# ProProject_ADS1292R-TestBoard.net
KiCad netlist of a schematic drawn in EasyEDA Pro
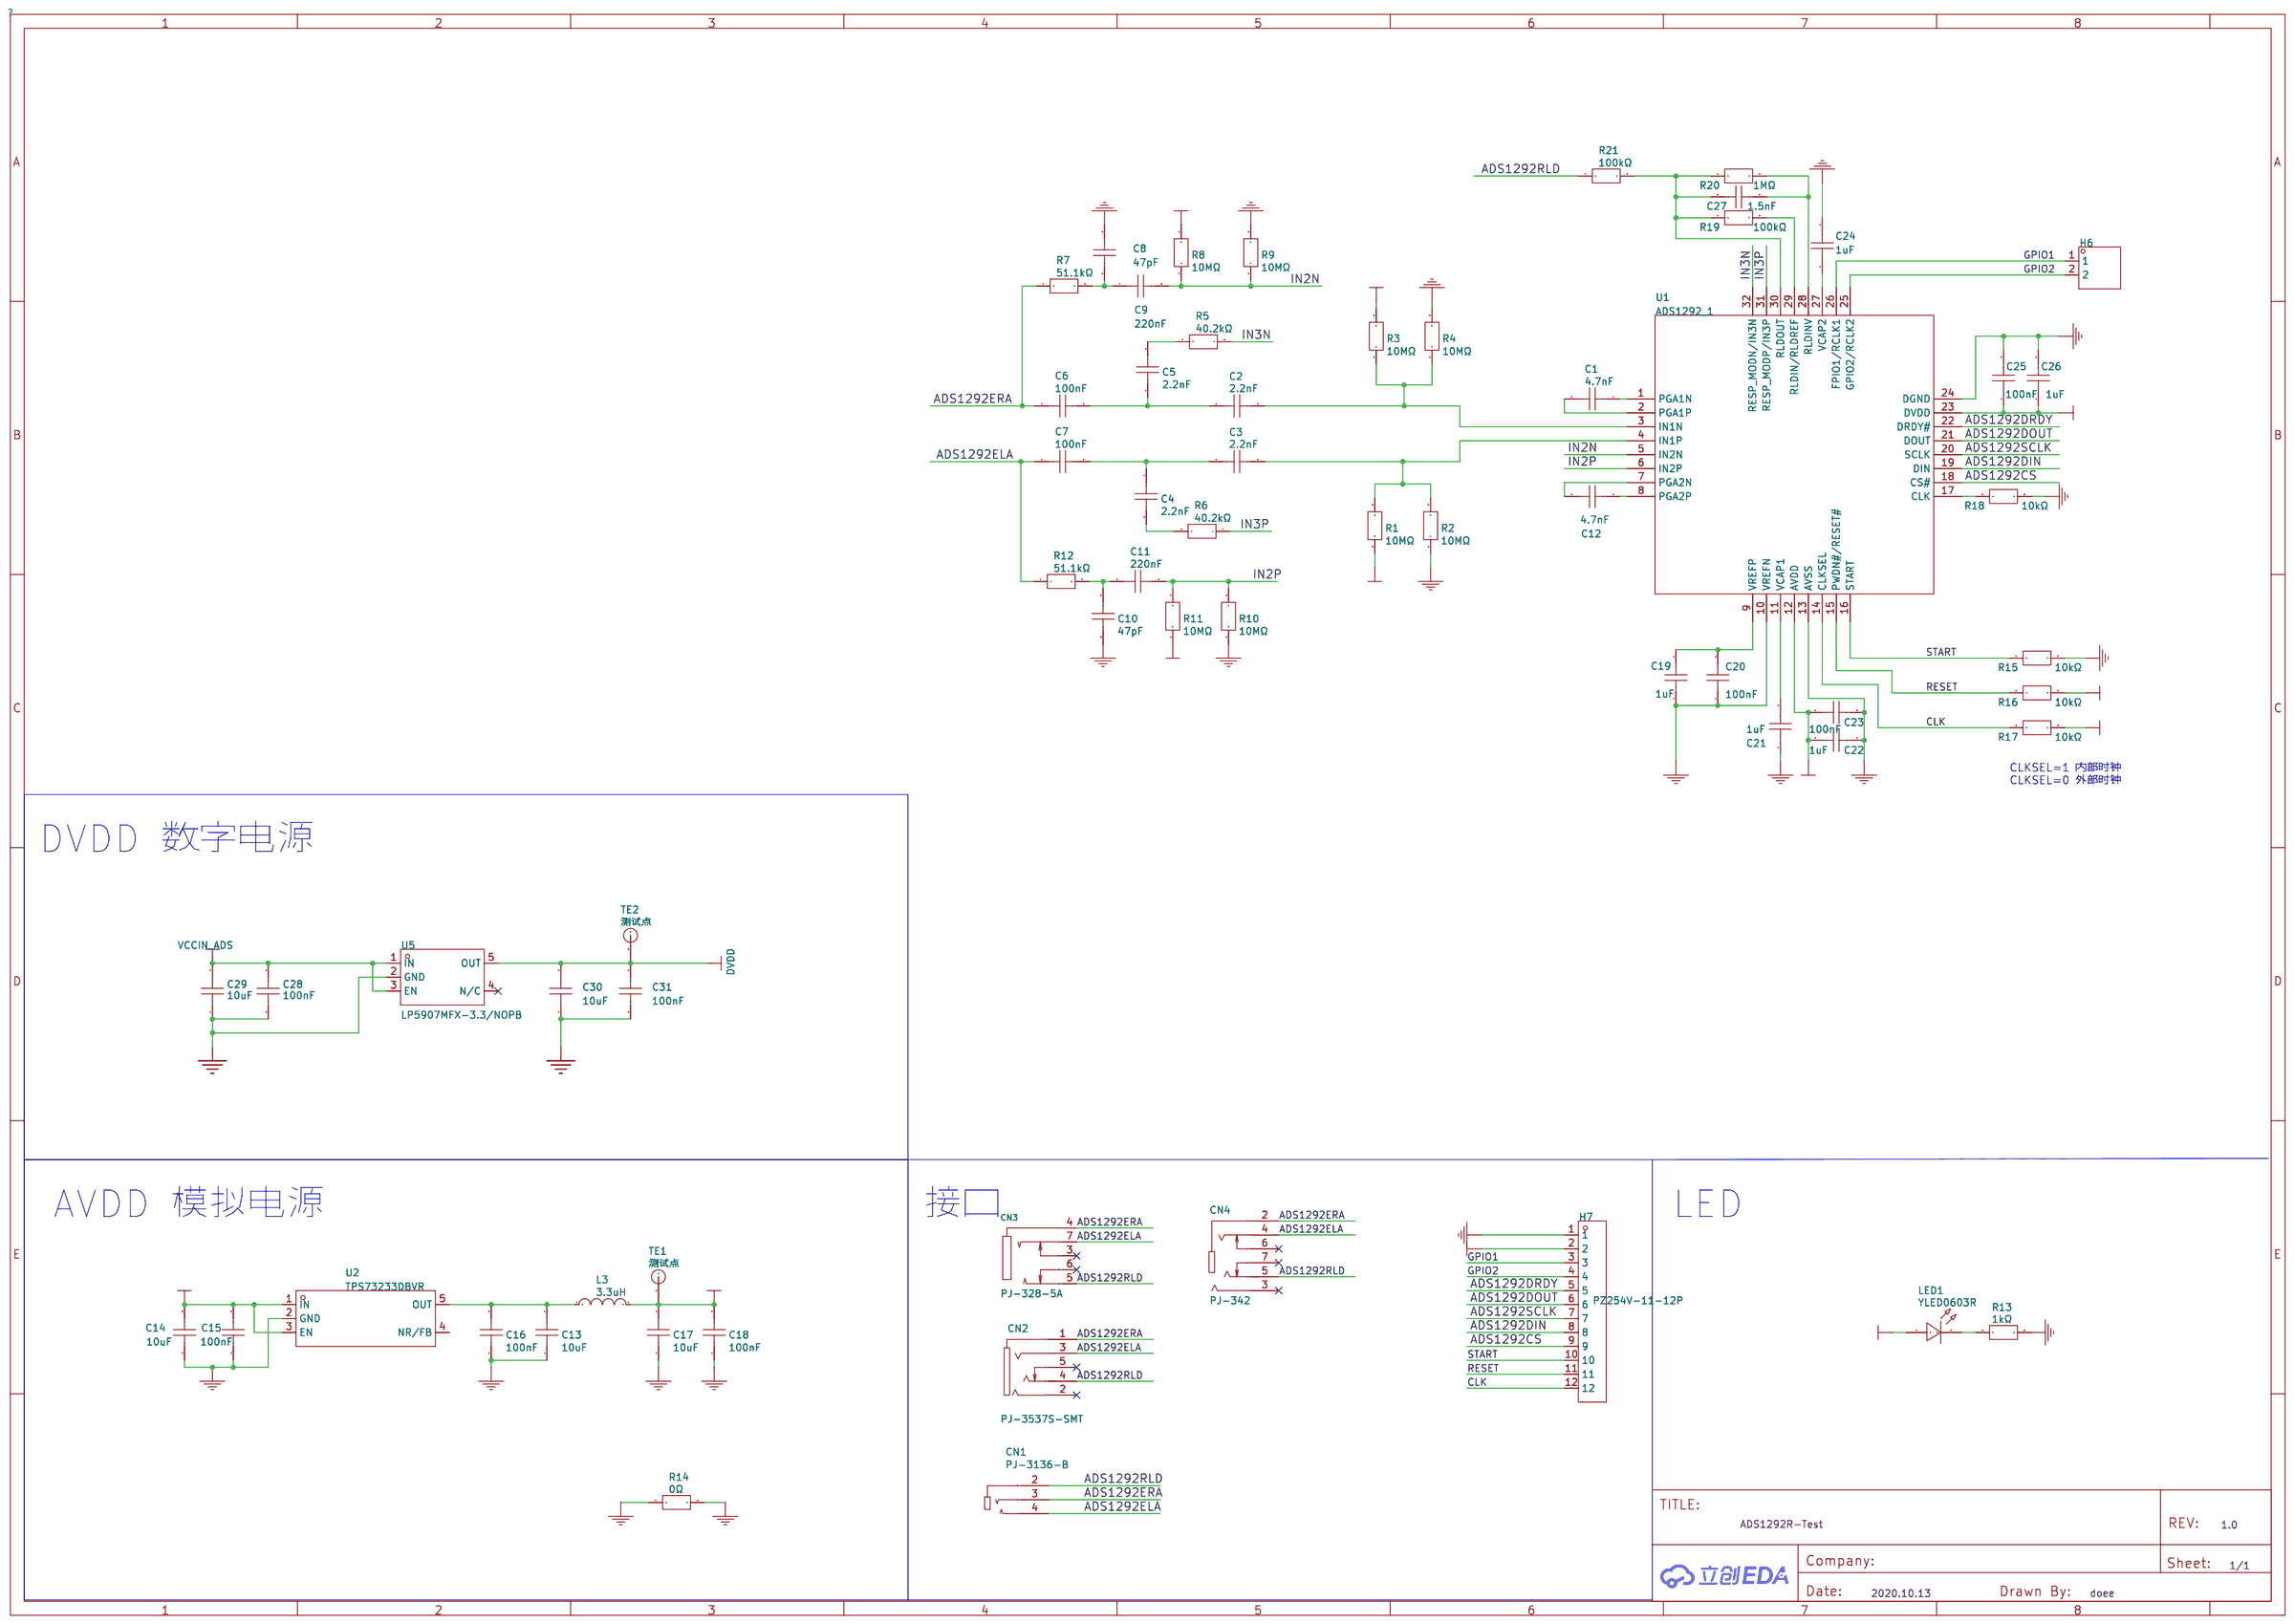
[diagram p0: schematic sheet]

(export (version "E")
  (design (tool "Eeschema 10.0.6"))
  (components
    (comp (ref "C1")
      (value "4.7nF")
      (footprint "easyedapro:C0603")
      (description "容值:4.7nF;精度:±5%;额定电压:50V;材质(温度系数):X7R;")
      (fields
        (field (name "Manufacturer Part") "CC0603JRX7R9BB472")
        (field (name "Manufacturer") "YAGEO(国巨)")
      )
      (libsource (lib "easyedapro") (part "4.7n"))
    )
    (comp (ref "C2")
      (value "2.2nF")
      (footprint "easyedapro:C0603")
      (description "容值:2.2nF;精度:±5%;额定电压:50V;材质(温度系数):NP0;")
      (fields
        (field (name "Manufacturer Part") "CC0603JRNPO9BN222")
        (field (name "Manufacturer") "YAGEO(国巨)")
      )
      (libsource (lib "easyedapro") (part "2.2n"))
    )
    (comp (ref "C3")
      (value "2.2nF")
      (footprint "easyedapro:C0603")
      (description "容值:2.2nF;精度:±5%;额定电压:50V;材质(温度系数):NP0;")
      (fields
        (field (name "Manufacturer Part") "CC0603JRNPO9BN222")
        (field (name "Manufacturer") "YAGEO(国巨)")
      )
      (libsource (lib "easyedapro") (part "2.2n"))
    )
    (comp (ref "C4")
      (value "2.2nF")
      (footprint "easyedapro:C0603")
      (description "容值:2.2nF;精度:±5%;额定电压:50V;材质(温度系数):NP0;")
      (fields
        (field (name "Manufacturer Part") "CC0603JRNPO9BN222")
        (field (name "Manufacturer") "YAGEO(国巨)")
      )
      (libsource (lib "easyedapro") (part "2.2n"))
    )
    (comp (ref "C5")
      (value "2.2nF")
      (footprint "easyedapro:C0603")
      (description "容值:2.2nF;精度:±5%;额定电压:50V;材质(温度系数):NP0;")
      (fields
        (field (name "Manufacturer Part") "CC0603JRNPO9BN222")
        (field (name "Manufacturer") "YAGEO(国巨)")
      )
      (libsource (lib "easyedapro") (part "2.2n"))
    )
    (comp (ref "C6")
      (value "100nF")
      (footprint "easyedapro:C0603")
      (description "容值:100nF;精度:±10%;额定电压:50V;材质(温度系数):X7R;")
      (fields
        (field (name "Manufacturer Part") "CC0603KRX7R9BB104")
        (field (name "Manufacturer") "YAGEO(国巨)")
      )
      (libsource (lib "easyedapro") (part "0.1u"))
    )
    (comp (ref "C7")
      (value "100nF")
      (footprint "easyedapro:C0603")
      (description "容值:100nF;精度:±10%;额定电压:50V;材质(温度系数):X7R;")
      (fields
        (field (name "Manufacturer Part") "CC0603KRX7R9BB104")
        (field (name "Manufacturer") "YAGEO(国巨)")
      )
      (libsource (lib "easyedapro") (part "0.1u"))
    )
    (comp (ref "C8")
      (value "47pF")
      (footprint "easyedapro:C0603")
      (description "容值:47pF;精度:±5%;额定电压:50V;材质(温度系数):C0G;")
      (fields
        (field (name "Manufacturer Part") "CL10C470JB8NNNC")
        (field (name "Manufacturer") "SAMSUNG(三星)")
      )
      (libsource (lib "easyedapro") (part "47p"))
    )
    (comp (ref "C9")
      (value "220nF")
      (footprint "easyedapro:C0603")
      (description "容值:220nF;精度:±10%;额定电压:25V;材质(温度系数):X7R;")
      (fields
        (field (name "Manufacturer Part") "CL10B224KA8NNNC")
        (field (name "Manufacturer") "SAMSUNG(三星)")
      )
      (libsource (lib "easyedapro") (part "220n"))
    )
    (comp (ref "C10")
      (value "47pF")
      (footprint "easyedapro:C0603")
      (description "容值:47pF;精度:±5%;额定电压:50V;材质(温度系数):C0G;")
      (fields
        (field (name "Manufacturer Part") "CL10C470JB8NNNC")
        (field (name "Manufacturer") "SAMSUNG(三星)")
      )
      (libsource (lib "easyedapro") (part "47p"))
    )
    (comp (ref "C11")
      (value "220nF")
      (footprint "easyedapro:C0603")
      (description "容值:220nF;精度:±10%;额定电压:25V;材质(温度系数):X7R;")
      (fields
        (field (name "Manufacturer Part") "CL10B224KA8NNNC")
        (field (name "Manufacturer") "SAMSUNG(三星)")
      )
      (libsource (lib "easyedapro") (part "220n"))
    )
    (comp (ref "C12")
      (value "4.7nF")
      (footprint "easyedapro:C0603")
      (description "容值:4.7nF;精度:±5%;额定电压:50V;材质(温度系数):X7R;")
      (fields
        (field (name "Manufacturer Part") "CC0603JRX7R9BB472")
        (field (name "Manufacturer") "YAGEO(国巨)")
      )
      (libsource (lib "easyedapro") (part "4.7n"))
    )
    (comp (ref "C13")
      (value "10uF")
      (footprint "easyedapro:C0603")
      (description "容值:10uF;精度:±10%;额定电压:10V;材质(温度系数):X5R;")
      (fields
        (field (name "Manufacturer Part") "CL10A106KP8NNNC")
        (field (name "Manufacturer") "SAMSUNG(三星)")
      )
      (libsource (lib "easyedapro") (part "10u"))
    )
    (comp (ref "C14")
      (value "10uF")
      (footprint "easyedapro:C0603")
      (description "容值:10uF;精度:±10%;额定电压:10V;材质(温度系数):X5R;")
      (fields
        (field (name "Manufacturer Part") "CL10A106KP8NNNC")
        (field (name "Manufacturer") "SAMSUNG(三星)")
      )
      (libsource (lib "easyedapro") (part "10u"))
    )
    (comp (ref "C15")
      (value "100nF")
      (footprint "easyedapro:C0603")
      (description "容值:100nF;精度:±10%;额定电压:50V;材质(温度系数):X7R;")
      (fields
        (field (name "Manufacturer Part") "CC0603KRX7R9BB104")
        (field (name "Manufacturer") "YAGEO(国巨)")
      )
      (libsource (lib "easyedapro") (part "0.1u"))
    )
    (comp (ref "C16")
      (value "100nF")
      (footprint "easyedapro:C0603")
      (description "容值:100nF;精度:±10%;额定电压:50V;材质(温度系数):X7R;")
      (fields
        (field (name "Manufacturer Part") "CC0603KRX7R9BB104")
        (field (name "Manufacturer") "YAGEO(国巨)")
      )
      (libsource (lib "easyedapro") (part "0.1u"))
    )
    (comp (ref "C17")
      (value "10uF")
      (footprint "easyedapro:C0603")
      (description "容值:10uF;精度:±10%;额定电压:10V;材质(温度系数):X5R;")
      (fields
        (field (name "Manufacturer Part") "CL10A106KP8NNNC")
        (field (name "Manufacturer") "SAMSUNG(三星)")
      )
      (libsource (lib "easyedapro") (part "10u"))
    )
    (comp (ref "C18")
      (value "100nF")
      (footprint "easyedapro:C0603")
      (description "容值:100nF;精度:±10%;额定电压:50V;材质(温度系数):X7R;")
      (fields
        (field (name "Manufacturer Part") "CC0603KRX7R9BB104")
        (field (name "Manufacturer") "YAGEO(国巨)")
      )
      (libsource (lib "easyedapro") (part "0.1u"))
    )
    (comp (ref "C19")
      (value "1uF")
      (footprint "easyedapro:C0603")
      (description "容值:1uF;精度:±10%;额定电压:50V;材质(温度系数):X5R;")
      (fields
        (field (name "Manufacturer Part") "CL10A105KB8NNNC")
        (field (name "Manufacturer") "SAMSUNG(三星)")
      )
      (libsource (lib "easyedapro") (part "1u"))
    )
    (comp (ref "C20")
      (value "100nF")
      (footprint "easyedapro:C0603")
      (description "容值:100nF;精度:±10%;额定电压:50V;材质(温度系数):X7R;")
      (fields
        (field (name "Manufacturer Part") "CC0603KRX7R9BB104")
        (field (name "Manufacturer") "YAGEO(国巨)")
      )
      (libsource (lib "easyedapro") (part "0.1u"))
    )
    (comp (ref "C21")
      (value "1uF")
      (footprint "easyedapro:C0603")
      (description "容值:1uF;精度:±10%;额定电压:50V;材质(温度系数):X5R;")
      (fields
        (field (name "Manufacturer Part") "CL10A105KB8NNNC")
        (field (name "Manufacturer") "SAMSUNG(三星)")
      )
      (libsource (lib "easyedapro") (part "1u"))
    )
    (comp (ref "C22")
      (value "1uF")
      (footprint "easyedapro:C0603")
      (description "容值:1uF;精度:±10%;额定电压:50V;材质(温度系数):X5R;")
      (fields
        (field (name "Manufacturer Part") "CL10A105KB8NNNC")
        (field (name "Manufacturer") "SAMSUNG(三星)")
      )
      (libsource (lib "easyedapro") (part "1u"))
    )
    (comp (ref "C23")
      (value "100nF")
      (footprint "easyedapro:C0603")
      (description "容值:100nF;精度:±10%;额定电压:50V;材质(温度系数):X7R;")
      (fields
        (field (name "Manufacturer Part") "CC0603KRX7R9BB104")
        (field (name "Manufacturer") "YAGEO(国巨)")
      )
      (libsource (lib "easyedapro") (part "0.1u"))
    )
    (comp (ref "C24")
      (value "1uF")
      (footprint "easyedapro:C0603")
      (description "容值:1uF;精度:±10%;额定电压:50V;材质(温度系数):X5R;")
      (fields
        (field (name "Manufacturer Part") "CL10A105KB8NNNC")
        (field (name "Manufacturer") "SAMSUNG(三星)")
      )
      (libsource (lib "easyedapro") (part "1u"))
    )
    (comp (ref "C25")
      (value "100nF")
      (footprint "easyedapro:C0603")
      (description "容值:100nF;精度:±10%;额定电压:50V;材质(温度系数):X7R;")
      (fields
        (field (name "Manufacturer Part") "CC0603KRX7R9BB104")
        (field (name "Manufacturer") "YAGEO(国巨)")
      )
      (libsource (lib "easyedapro") (part "0.1u"))
    )
    (comp (ref "C26")
      (value "1uF")
      (footprint "easyedapro:C0603")
      (description "容值:1uF;精度:±10%;额定电压:50V;材质(温度系数):X5R;")
      (fields
        (field (name "Manufacturer Part") "CL10A105KB8NNNC")
        (field (name "Manufacturer") "SAMSUNG(三星)")
      )
      (libsource (lib "easyedapro") (part "1u"))
    )
    (comp (ref "C27")
      (value "1.5nF")
      (footprint "easyedapro:C0603")
      (description "容值:1.5nF;精度:±10%;额定电压:50V;材质(温度系数):-;")
      (fields (field (name "Manufacturer") "SAMSUNG(三星)") (field (name "Tolerance") "±10%"))
      (libsource (lib "easyedapro") (part "1.5n"))
    )
    (comp (ref "C28")
      (value "100nF")
      (footprint "easyedapro:C0603")
      (fields
        (field (name "Manufacturer Part") "CC0603KRX7R9BB104")
        (field (name "Manufacturer") "YAGEO(国巨)")
        (field (name "Tolerance") "±10%")
      )
      (libsource (lib "easyedapro") (part "CapAcitance"))
    )
    (comp (ref "C29")
      (value "10uF")
      (footprint "easyedapro:C0603")
      (fields
        (field (name "Manufacturer Part") "CL10A106KP8NNNC")
        (field (name "Manufacturer") "SAMSUNG(三星)")
        (field (name "Tolerance") "±10%")
      )
      (libsource (lib "easyedapro") (part "CapAcitance"))
    )
    (comp (ref "C30")
      (value "10uF")
      (footprint "easyedapro:C0603")
      (fields
        (field (name "Manufacturer Part") "CL10A106KP8NNNC")
        (field (name "Manufacturer") "SAMSUNG(三星)")
        (field (name "Tolerance") "±10%")
      )
      (libsource (lib "easyedapro") (part "CapAcitance"))
    )
    (comp (ref "C31")
      (value "100nF")
      (footprint "easyedapro:C0603")
      (fields
        (field (name "Manufacturer Part") "CC0603KRX7R9BB104")
        (field (name "Manufacturer") "YAGEO(国巨)")
        (field (name "Tolerance") "±10%")
      )
      (libsource (lib "easyedapro") (part "CapAcitance"))
    )
    (comp (ref "CN1")
      (value "PJ-3136-B")
      (footprint "easyedapro:AUDIO-TH_PJ-3136-B")
      (libsource (lib "easyedapro") (part "PJ-3136-B"))
    )
    (comp (ref "CN2")
      (value "PJ-3537S-SMT")
      (footprint "easyedapro:AUDIO-SMD_PJ-3537S")
      (description "连接器类型:3.5mm耳机座;额定电流:500mA;额定电压:30V;工作温度范围:-30°C~+70°C;焊接温度(最大值):235°C;")
      (fields (field (name "Manufacturer") "XKB Connectivity(中国星坤)"))
      (libsource (lib "easyedapro") (part "PJ-3537S"))
    )
    (comp (ref "CN3")
      (value "PJ-328-5A")
      (footprint "easyedapro:AUDIO-SMD_PJ-328-5A")
      (description "连接器类型:3.5mm耳机座;额定电流:500mA;额定电压:30V;工作温度范围:-20°C~+70°C;")
      (fields (field (name "Manufacturer") "韩国韩荣"))
      (libsource (lib "easyedapro") (part "PJ-328-5A"))
    )
    (comp (ref "CN4")
      (value "PJ-342")
      (footprint "easyedapro:AUDIO-SMD_PJ-342")
      (description "连接器类型:3.5mm耳机座;额定电流:500mA;额定电压:30V;工作温度范围:-30°C~+70°C;")
      (fields (field (name "Manufacturer") "SHOU HAN(首韩)"))
      (libsource (lib "easyedapro") (part "PJ-342"))
    )
    (comp (ref "H6")
      (value "~")
      (footprint "easyedapro:HDR-TH_2P-P2.54-V-M-1")
      (libsource (lib "easyedapro") (part "210S-1*2P L=11.6MMGold-plated black"))
    )
    (comp (ref "H7")
      (value "PZ254V-11-12P")
      (footprint "easyedapro:HDR-TH_12P-P2.54-V-M")
      (fields (field (name "Manufacturer") "XFCN(兴飞)"))
      (libsource (lib "easyedapro") (part "HDR_2.54-1x12P"))
    )
    (comp (ref "L3")
      (value "3.3uH")
      (footprint "easyedapro:L0805")
      (libsource (lib "easyedapro") (part "3.3uH"))
    )
    (comp (ref "LED1")
      (value "YLED0603R")
      (footprint "easyedapro:LED0603_RED")
      (fields (field (name "Manufacturer") "YONGYUTAI(永裕泰)"))
      (libsource (lib "easyedapro") (part "LED-0603_R"))
    )
    (comp (ref "R1")
      (value "10MΩ")
      (footprint "easyedapro:R0603")
      (description "电阻类型:厚膜电阻;阻值:10MΩ;精度:±1%;功率:100mW;最大工作电压:75V;温度系数:±100ppm/℃;")
      (fields
        (field (name "Manufacturer Part") "0603WAF1005T5E")
        (field (name "Manufacturer") "UNI-ROYAL(厚声)")
      )
      (libsource (lib "easyedapro") (part "10M"))
    )
    (comp (ref "R2")
      (value "10MΩ")
      (footprint "easyedapro:R0603")
      (description "电阻类型:厚膜电阻;阻值:10MΩ;精度:±1%;功率:100mW;最大工作电压:75V;温度系数:±100ppm/℃;")
      (fields
        (field (name "Manufacturer Part") "0603WAF1005T5E")
        (field (name "Manufacturer") "UNI-ROYAL(厚声)")
      )
      (libsource (lib "easyedapro") (part "10M"))
    )
    (comp (ref "R3")
      (value "10MΩ")
      (footprint "easyedapro:R0603")
      (description "电阻类型:厚膜电阻;阻值:10MΩ;精度:±1%;功率:100mW;最大工作电压:75V;温度系数:±100ppm/℃;")
      (fields
        (field (name "Manufacturer Part") "0603WAF1005T5E")
        (field (name "Manufacturer") "UNI-ROYAL(厚声)")
      )
      (libsource (lib "easyedapro") (part "10M"))
    )
    (comp (ref "R4")
      (value "10MΩ")
      (footprint "easyedapro:R0603")
      (description "电阻类型:厚膜电阻;阻值:10MΩ;精度:±1%;功率:100mW;最大工作电压:75V;温度系数:±100ppm/℃;")
      (fields
        (field (name "Manufacturer Part") "0603WAF1005T5E")
        (field (name "Manufacturer") "UNI-ROYAL(厚声)")
      )
      (libsource (lib "easyedapro") (part "10M"))
    )
    (comp (ref "R5")
      (value "40.2kΩ")
      (footprint "easyedapro:R0603")
      (description "电阻类型:厚膜电阻;阻值:40.2kΩ;精度:±1%;功率:100mW;最大工作电压:75V;温度系数:±100ppm/℃;")
      (fields
        (field (name "Manufacturer Part") "0603WAF4022T5E")
        (field (name "Manufacturer") "UNI-ROYAL(厚声)")
      )
      (libsource (lib "easyedapro") (part "40.2k"))
    )
    (comp (ref "R6")
      (value "40.2kΩ")
      (footprint "easyedapro:R0603")
      (description "电阻类型:厚膜电阻;阻值:40.2kΩ;精度:±1%;功率:100mW;最大工作电压:75V;温度系数:±100ppm/℃;")
      (fields
        (field (name "Manufacturer Part") "0603WAF4022T5E")
        (field (name "Manufacturer") "UNI-ROYAL(厚声)")
      )
      (libsource (lib "easyedapro") (part "40.2k"))
    )
    (comp (ref "R7")
      (value "51.1kΩ")
      (footprint "easyedapro:R0603")
      (description "电阻类型:厚膜电阻;阻值:51.1kΩ;精度:±1%;功率:100mW;最大工作电压:75V;温度系数:±100ppm/℃;")
      (fields
        (field (name "Manufacturer Part") "0603WAF5112T5E")
        (field (name "Manufacturer") "UNI-ROYAL(厚声)")
      )
      (libsource (lib "easyedapro") (part "51.1k"))
    )
    (comp (ref "R8")
      (value "10MΩ")
      (footprint "easyedapro:R0603")
      (description "电阻类型:厚膜电阻;阻值:10MΩ;精度:±1%;功率:100mW;最大工作电压:75V;温度系数:±100ppm/℃;")
      (fields
        (field (name "Manufacturer Part") "0603WAF1005T5E")
        (field (name "Manufacturer") "UNI-ROYAL(厚声)")
      )
      (libsource (lib "easyedapro") (part "10M"))
    )
    (comp (ref "R9")
      (value "10MΩ")
      (footprint "easyedapro:R0603")
      (description "电阻类型:厚膜电阻;阻值:10MΩ;精度:±1%;功率:100mW;最大工作电压:75V;温度系数:±100ppm/℃;")
      (fields
        (field (name "Manufacturer Part") "0603WAF1005T5E")
        (field (name "Manufacturer") "UNI-ROYAL(厚声)")
      )
      (libsource (lib "easyedapro") (part "10M"))
    )
    (comp (ref "R10")
      (value "10MΩ")
      (footprint "easyedapro:R0603")
      (description "电阻类型:厚膜电阻;阻值:10MΩ;精度:±1%;功率:100mW;最大工作电压:75V;温度系数:±100ppm/℃;")
      (fields
        (field (name "Manufacturer Part") "0603WAF1005T5E")
        (field (name "Manufacturer") "UNI-ROYAL(厚声)")
      )
      (libsource (lib "easyedapro") (part "10M"))
    )
    (comp (ref "R11")
      (value "10MΩ")
      (footprint "easyedapro:R0603")
      (description "电阻类型:厚膜电阻;阻值:10MΩ;精度:±1%;功率:100mW;最大工作电压:75V;温度系数:±100ppm/℃;")
      (fields
        (field (name "Manufacturer Part") "0603WAF1005T5E")
        (field (name "Manufacturer") "UNI-ROYAL(厚声)")
      )
      (libsource (lib "easyedapro") (part "10M"))
    )
    (comp (ref "R12")
      (value "51.1kΩ")
      (footprint "easyedapro:R0603")
      (description "电阻类型:厚膜电阻;阻值:51.1kΩ;精度:±1%;功率:100mW;最大工作电压:75V;温度系数:±100ppm/℃;")
      (fields
        (field (name "Manufacturer Part") "0603WAF5112T5E")
        (field (name "Manufacturer") "UNI-ROYAL(厚声)")
      )
      (libsource (lib "easyedapro") (part "51.1k"))
    )
    (comp (ref "R13")
      (value "1kΩ")
      (footprint "easyedapro:R0603")
      (description "电阻类型:厚膜电阻;阻值:1kΩ;精度:±1%;功率:100mW;最大工作电压:75V;温度系数:±100ppm/℃;")
      (fields (field (name "Manufacturer Part") "RC0603FR-071KL") (field (name "Manufacturer") "YAGEO(国巨)"))
      (libsource (lib "easyedapro") (part "1K"))
    )
    (comp (ref "R14")
      (value "0Ω")
      (footprint "easyedapro:R0603")
      (description "电阻类型:厚膜电阻;阻值:0Ω;精度:±1%;功率:100mW;最大工作电压:75V;")
      (fields
        (field (name "Manufacturer Part") "0603WAF0000T5E")
        (field (name "Manufacturer") "UNI-ROYAL(厚声)")
      )
      (libsource (lib "easyedapro") (part "0Ω"))
    )
    (comp (ref "R15")
      (value "10kΩ")
      (footprint "easyedapro:R0603")
      (description "电阻类型:厚膜电阻;阻值:10kΩ;精度:±1%;功率:100mW;最大工作电压:75V;温度系数:±100ppm/℃;")
      (fields
        (field (name "Manufacturer Part") "0603WAF1002T5E")
        (field (name "Manufacturer") "UNI-ROYAL(厚声)")
      )
      (libsource (lib "easyedapro") (part "10k"))
    )
    (comp (ref "R16")
      (value "10kΩ")
      (footprint "easyedapro:R0603")
      (description "电阻类型:厚膜电阻;阻值:10kΩ;精度:±1%;功率:100mW;最大工作电压:75V;温度系数:±100ppm/℃;")
      (fields
        (field (name "Manufacturer Part") "0603WAF1002T5E")
        (field (name "Manufacturer") "UNI-ROYAL(厚声)")
      )
      (libsource (lib "easyedapro") (part "10k"))
    )
    (comp (ref "R17")
      (value "10kΩ")
      (footprint "easyedapro:R0603")
      (description "电阻类型:厚膜电阻;阻值:10kΩ;精度:±1%;功率:100mW;最大工作电压:75V;温度系数:±100ppm/℃;")
      (fields
        (field (name "Manufacturer Part") "0603WAF1002T5E")
        (field (name "Manufacturer") "UNI-ROYAL(厚声)")
      )
      (libsource (lib "easyedapro") (part "10k"))
    )
    (comp (ref "R18")
      (value "10kΩ")
      (footprint "easyedapro:R0603")
      (description "电阻类型:厚膜电阻;阻值:10kΩ;精度:±1%;功率:100mW;最大工作电压:75V;温度系数:±100ppm/℃;")
      (fields
        (field (name "Manufacturer Part") "0603WAF1002T5E")
        (field (name "Manufacturer") "UNI-ROYAL(厚声)")
      )
      (libsource (lib "easyedapro") (part "10k"))
    )
    (comp (ref "R19")
      (value "100kΩ")
      (footprint "easyedapro:R0603")
      (description "电阻类型:厚膜电阻;阻值:100kΩ;精度:±1%;功率:100mW;最大工作电压:75V;温度系数:±100ppm/℃;")
      (fields (field (name "Manufacturer Part") "RC0603FR-07100KL") (field (name "Manufacturer") "YAGEO(国巨)"))
      (libsource (lib "easyedapro") (part "100k"))
    )
    (comp (ref "R20")
      (value "1MΩ")
      (footprint "easyedapro:R0603")
      (description "电阻类型:厚膜电阻;阻值:1MΩ;精度:±1%;功率:100mW;最大工作电压:75V;温度系数:±100ppm/℃;")
      (fields
        (field (name "Manufacturer Part") "0603WAF1004T5E")
        (field (name "Manufacturer") "UNI-ROYAL(厚声)")
      )
      (libsource (lib "easyedapro") (part "1M"))
    )
    (comp (ref "R21")
      (value "100kΩ")
      (footprint "easyedapro:R0603")
      (description "电阻类型:厚膜电阻;阻值:100kΩ;精度:±1%;功率:100mW;最大工作电压:75V;温度系数:±100ppm/℃;")
      (fields (field (name "Manufacturer Part") "RC0603FR-07100KL") (field (name "Manufacturer") "YAGEO(国巨)"))
      (libsource (lib "easyedapro") (part "100k"))
    )
    (comp (ref "TE1") (value "测试点") (footprint "easyedapro:测试点") (libsource (lib "easyedapro") (part "测试点")))
    (comp (ref "TE2") (value "测试点") (footprint "easyedapro:测试点") (libsource (lib "easyedapro") (part "测试点")))
    (comp (ref "U1")
      (value "ADS1292_1")
      (footprint "easyedapro:TQFP-32_L5.0-W5.0-P0.50-LS7.0-TL")
      (libsource (lib "easyedapro") (part "ADS1292_1"))
    )
    (comp (ref "U2")
      (value "TPS73233DBVR")
      (footprint "easyedapro:SOT-23-5_L3.0-W1.7-P0.95-LS2.8-BL")
      (description "输出类型:固定;最大输入电压:5.5V;输出电压:3.3V;最大输出电流:250mA;电源纹波抑制比(PSRR):58dB;输出极性:正极;")
      (fields (field (name "Manufacturer") "TI(德州仪器)"))
      (libsource (lib "easyedapro") (part "TPS73233DBVR"))
    )
    (comp (ref "U5")
      (value "LP5907MFX-3.3/NOPB")
      (footprint "easyedapro:SOT-23-5_L3.0-W1.7-P0.95-LS2.8-BR")
      (description "输出类型:固定;最大输入电压:5.5V;输出电压:3.3V;最大输出电流:250mA;电源纹波抑制比(PSRR):90dB;输出极性:正极;")
      (fields (field (name "Manufacturer") "TI(德州仪器)"))
      (libsource (lib "easyedapro") (part "LP5907MFX-3.3/NOPB"))
    )
  )
  (nets
    (net (code "1") (name "/ADS1292CS") (class "Default")
      (node (ref "H7") (pin "9") (pinfunction "9_9") (pintype "input"))
      (node (ref "U1") (pin "18") (pinfunction "CS#_18") (pintype "unspecified"))
    )
    (net (code "2") (name "/ADS1292DIN") (class "Default")
      (node (ref "H7") (pin "8") (pinfunction "8_8") (pintype "input"))
      (node (ref "U1") (pin "19") (pinfunction "DIN_19") (pintype "unspecified"))
    )
    (net (code "3") (name "/ADS1292DOUT") (class "Default")
      (node (ref "H7") (pin "6") (pinfunction "6_6") (pintype "input"))
      (node (ref "U1") (pin "21") (pinfunction "DOUT_21") (pintype "unspecified"))
    )
    (net (code "4") (name "/ADS1292DRDY") (class "Default")
      (node (ref "H7") (pin "5") (pinfunction "5_5") (pintype "input"))
      (node (ref "U1") (pin "22") (pinfunction "DRDY#_22") (pintype "unspecified"))
    )
    (net (code "5") (name "/ADS1292ELA") (class "Default")
      (node (ref "C7") (pin "1") (pinfunction "1_1") (pintype "unspecified"))
      (node (ref "CN1") (pin "4") (pinfunction "4_4") (pintype "unspecified"))
      (node (ref "CN2") (pin "3") (pinfunction "3_3") (pintype "input"))
      (node (ref "CN3") (pin "7") (pinfunction "7_7") (pintype "input"))
      (node (ref "CN4") (pin "4") (pinfunction "4_4") (pintype "unspecified"))
      (node (ref "R12") (pin "1") (pinfunction "1_1") (pintype "unspecified"))
    )
    (net (code "6") (name "/ADS1292ERA") (class "Default")
      (node (ref "C6") (pin "1") (pinfunction "1_1") (pintype "unspecified"))
      (node (ref "CN1") (pin "3") (pinfunction "3_3") (pintype "unspecified"))
      (node (ref "CN2") (pin "1") (pinfunction "1_1") (pintype "input"))
      (node (ref "CN3") (pin "4") (pinfunction "4_4") (pintype "input"))
      (node (ref "CN4") (pin "2") (pinfunction "2_2") (pintype "unspecified"))
      (node (ref "R7") (pin "1") (pinfunction "1_1") (pintype "unspecified"))
    )
    (net (code "7") (name "/ADS1292RLD") (class "Default")
      (node (ref "CN1") (pin "2") (pinfunction "2_2") (pintype "unspecified"))
      (node (ref "CN2") (pin "4") (pinfunction "4_4") (pintype "input"))
      (node (ref "CN3") (pin "5") (pinfunction "5_5") (pintype "input"))
      (node (ref "CN4") (pin "5") (pinfunction "5_5") (pintype "unspecified"))
      (node (ref "R21") (pin "1") (pinfunction "1_1") (pintype "unspecified"))
    )
    (net (code "8") (name "/ADS1292SCLK") (class "Default")
      (node (ref "H7") (pin "7") (pinfunction "7_7") (pintype "input"))
      (node (ref "U1") (pin "20") (pinfunction "SCLK_20") (pintype "unspecified"))
    )
    (net (code "9") (name "/CLK") (class "Default")
      (node (ref "H7") (pin "12") (pinfunction "12_12") (pintype "input"))
      (node (ref "R17") (pin "1") (pinfunction "1_1") (pintype "unspecified"))
      (node (ref "U1") (pin "14") (pinfunction "CLKSEL_14") (pintype "unspecified"))
    )
    (net (code "10") (name "/GPIO1") (class "Default")
      (node (ref "H6") (pin "1") (pinfunction "1_1") (pintype "unspecified"))
      (node (ref "H7") (pin "3") (pinfunction "3_3") (pintype "input"))
      (node (ref "U1") (pin "26") (pinfunction "FPIO1/RCLK1_26") (pintype "unspecified"))
    )
    (net (code "11") (name "/GPIO2") (class "Default")
      (node (ref "H6") (pin "2") (pinfunction "2_2") (pintype "unspecified"))
      (node (ref "H7") (pin "4") (pinfunction "4_4") (pintype "input"))
      (node (ref "U1") (pin "25") (pinfunction "GPIO2/RCLK2_25") (pintype "unspecified"))
    )
    (net (code "12") (name "/IN2N") (class "Default")
      (node (ref "C9") (pin "2") (pinfunction "2_2") (pintype "unspecified"))
      (node (ref "R8") (pin "1") (pinfunction "1_1") (pintype "unspecified"))
      (node (ref "R9") (pin "1") (pinfunction "1_1") (pintype "unspecified"))
      (node (ref "U1") (pin "5") (pinfunction "IN2N_5") (pintype "unspecified"))
    )
    (net (code "13") (name "/IN2P") (class "Default")
      (node (ref "C11") (pin "2") (pinfunction "2_2") (pintype "unspecified"))
      (node (ref "R10") (pin "1") (pinfunction "1_1") (pintype "unspecified"))
      (node (ref "R11") (pin "1") (pinfunction "1_1") (pintype "unspecified"))
      (node (ref "U1") (pin "6") (pinfunction "IN2P_6") (pintype "unspecified"))
    )
    (net (code "14") (name "/IN3N") (class "Default")
      (node (ref "R5") (pin "2") (pinfunction "2_2") (pintype "unspecified"))
      (node (ref "U1") (pin "32") (pinfunction "RESP_MODN/IN3N_32") (pintype "unspecified"))
    )
    (net (code "15") (name "/IN3P") (class "Default")
      (node (ref "R6") (pin "1") (pinfunction "1_1") (pintype "unspecified"))
      (node (ref "U1") (pin "31") (pinfunction "RESP_MODP/IN3P_31") (pintype "unspecified"))
    )
    (net (code "16") (name "/RESET") (class "Default")
      (node (ref "H7") (pin "11") (pinfunction "11_11") (pintype "input"))
      (node (ref "R16") (pin "1") (pinfunction "1_1") (pintype "unspecified"))
      (node (ref "U1") (pin "15") (pinfunction "PWDN#/RESET#_15") (pintype "unspecified"))
    )
    (net (code "17") (name "/START") (class "Default")
      (node (ref "H7") (pin "10") (pinfunction "10_10") (pintype "input"))
      (node (ref "R15") (pin "1") (pinfunction "1_1") (pintype "unspecified"))
      (node (ref "U1") (pin "16") (pinfunction "START_16") (pintype "unspecified"))
    )
    (net (code "18") (name "AVDD") (class "Default")
      (node (ref "C17") (pin "2") (pinfunction "2_2") (pintype "unspecified"))
      (node (ref "C18") (pin "2") (pinfunction "2_2") (pintype "unspecified"))
      (node (ref "C22") (pin "2") (pinfunction "2_2") (pintype "unspecified"))
      (node (ref "C23") (pin "2") (pinfunction "2_2") (pintype "unspecified"))
      (node (ref "L3") (pin "2") (pinfunction "2_2") (pintype "unspecified"))
      (node (ref "R1") (pin "1") (pinfunction "1_1") (pintype "unspecified"))
      (node (ref "R11") (pin "2") (pinfunction "2_2") (pintype "unspecified"))
      (node (ref "R3") (pin "2") (pinfunction "2_2") (pintype "unspecified"))
      (node (ref "R8") (pin "2") (pinfunction "2_2") (pintype "unspecified"))
      (node (ref "TE1") (pin "1") (pinfunction "1_1") (pintype "unspecified"))
      (node (ref "U1") (pin "12") (pinfunction "AVDD_12") (pintype "unspecified"))
    )
    (net (code "19") (name "AVSS") (class "Default")
      (node (ref "C10") (pin "2") (pinfunction "2_2") (pintype "unspecified"))
      (node (ref "C18") (pin "1") (pinfunction "1_1") (pintype "unspecified"))
      (node (ref "C19") (pin "1") (pinfunction "1_1") (pintype "unspecified"))
      (node (ref "C20") (pin "1") (pinfunction "1_1") (pintype "unspecified"))
      (node (ref "C22") (pin "1") (pinfunction "1_1") (pintype "unspecified"))
      (node (ref "C23") (pin "1") (pinfunction "1_1") (pintype "unspecified"))
      (node (ref "C8") (pin "2") (pinfunction "2_2") (pintype "unspecified"))
      (node (ref "R10") (pin "2") (pinfunction "2_2") (pintype "unspecified"))
      (node (ref "R14") (pin "1") (pinfunction "1_1") (pintype "unspecified"))
      (node (ref "R2") (pin "1") (pinfunction "1_1") (pintype "unspecified"))
      (node (ref "R4") (pin "2") (pinfunction "2_2") (pintype "unspecified"))
      (node (ref "R9") (pin "2") (pinfunction "2_2") (pintype "unspecified"))
      (node (ref "U1") (pin "10") (pinfunction "VREFN_10") (pintype "unspecified"))
      (node (ref "U1") (pin "13") (pinfunction "AVSS_13") (pintype "unspecified"))
    )
    (net (code "20") (name "DVDD") (class "Default")
      (node (ref "C25") (pin "1") (pinfunction "1_1") (pintype "unspecified"))
      (node (ref "C26") (pin "1") (pinfunction "1_1") (pintype "unspecified"))
      (node (ref "C30") (pin "2") (pinfunction "2_2") (pintype "input"))
      (node (ref "C31") (pin "2") (pinfunction "2_2") (pintype "input"))
      (node (ref "LED1") (pin "1") (pinfunction "1_1") (pintype "unspecified"))
      (node (ref "R16") (pin "2") (pinfunction "2_2") (pintype "unspecified"))
      (node (ref "R17") (pin "2") (pinfunction "2_2") (pintype "unspecified"))
      (node (ref "TE2") (pin "1") (pinfunction "1_1") (pintype "unspecified"))
      (node (ref "U1") (pin "23") (pinfunction "DVDD_23") (pintype "unspecified"))
      (node (ref "U5") (pin "5") (pinfunction "OUT_5") (pintype "unspecified"))
    )
    (net (code "21") (name "GND") (class "Default")
      (node (ref "C13") (pin "1") (pinfunction "1_1") (pintype "unspecified"))
      (node (ref "C14") (pin "1") (pinfunction "1_1") (pintype "unspecified"))
      (node (ref "C15") (pin "1") (pinfunction "1_1") (pintype "unspecified"))
      (node (ref "C16") (pin "1") (pinfunction "1_1") (pintype "unspecified"))
      (node (ref "C17") (pin "1") (pinfunction "1_1") (pintype "unspecified"))
      (node (ref "C21") (pin "1") (pinfunction "1_1") (pintype "unspecified"))
      (node (ref "C24") (pin "1") (pinfunction "1_1") (pintype "unspecified"))
      (node (ref "C25") (pin "2") (pinfunction "2_2") (pintype "unspecified"))
      (node (ref "C26") (pin "2") (pinfunction "2_2") (pintype "unspecified"))
      (node (ref "C28") (pin "1") (pinfunction "1_1") (pintype "input"))
      (node (ref "C29") (pin "1") (pinfunction "1_1") (pintype "input"))
      (node (ref "C30") (pin "1") (pinfunction "1_1") (pintype "input"))
      (node (ref "C31") (pin "1") (pinfunction "1_1") (pintype "input"))
      (node (ref "H7") (pin "1") (pinfunction "1_1") (pintype "input"))
      (node (ref "R13") (pin "2") (pinfunction "2_2") (pintype "unspecified"))
      (node (ref "R14") (pin "2") (pinfunction "2_2") (pintype "unspecified"))
      (node (ref "R15") (pin "2") (pinfunction "2_2") (pintype "unspecified"))
      (node (ref "R18") (pin "2") (pinfunction "2_2") (pintype "unspecified"))
      (node (ref "U1") (pin "24") (pinfunction "DGND_24") (pintype "unspecified"))
      (node (ref "U2") (pin "2") (pinfunction "GND_2") (pintype "unspecified"))
      (node (ref "U5") (pin "2") (pinfunction "GND_2") (pintype "unspecified"))
    )
    (net (code "22") (name "Net-(C2-Pad1)") (class "Default")
      (node (ref "C2") (pin "1") (pinfunction "1_1") (pintype "unspecified"))
      (node (ref "C5") (pin "1") (pinfunction "1_1") (pintype "unspecified"))
      (node (ref "C6") (pin "2") (pinfunction "2_2") (pintype "unspecified"))
    )
    (net (code "23") (name "Net-(C3-Pad1)") (class "Default")
      (node (ref "C3") (pin "1") (pinfunction "1_1") (pintype "unspecified"))
      (node (ref "C4") (pin "1") (pinfunction "1_1") (pintype "unspecified"))
      (node (ref "C7") (pin "2") (pinfunction "2_2") (pintype "unspecified"))
    )
    (net (code "24") (name "Net-(C4-Pad2)") (class "Default")
      (node (ref "C4") (pin "2") (pinfunction "2_2") (pintype "unspecified"))
      (node (ref "R6") (pin "2") (pinfunction "2_2") (pintype "unspecified"))
    )
    (net (code "25") (name "Net-(C5-Pad2)") (class "Default")
      (node (ref "C5") (pin "2") (pinfunction "2_2") (pintype "unspecified"))
      (node (ref "R5") (pin "1") (pinfunction "1_1") (pintype "unspecified"))
    )
    (net (code "26") (name "Net-(C8-Pad1)") (class "Default")
      (node (ref "C8") (pin "1") (pinfunction "1_1") (pintype "unspecified"))
      (node (ref "C9") (pin "1") (pinfunction "1_1") (pintype "unspecified"))
      (node (ref "R7") (pin "2") (pinfunction "2_2") (pintype "unspecified"))
    )
    (net (code "27") (name "Net-(C10-Pad1)") (class "Default")
      (node (ref "C10") (pin "1") (pinfunction "1_1") (pintype "unspecified"))
      (node (ref "C11") (pin "1") (pinfunction "1_1") (pintype "unspecified"))
      (node (ref "R12") (pin "2") (pinfunction "2_2") (pintype "unspecified"))
    )
    (net (code "28") (name "Net-(LED1-Pad2)") (class "Default")
      (node (ref "LED1") (pin "2") (pinfunction "2_2") (pintype "unspecified"))
      (node (ref "R13") (pin "1") (pinfunction "1_1") (pintype "unspecified"))
    )
    (net (code "29") (name "Net-(U1-CLK)") (class "Default")
      (node (ref "R18") (pin "1") (pinfunction "1_1") (pintype "unspecified"))
      (node (ref "U1") (pin "17") (pinfunction "CLK_17") (pintype "unspecified"))
    )
    (net (code "30") (name "Net-(U1-IN1N)") (class "Default")
      (node (ref "C2") (pin "2") (pinfunction "2_2") (pintype "unspecified"))
      (node (ref "R3") (pin "1") (pinfunction "1_1") (pintype "unspecified"))
      (node (ref "R4") (pin "1") (pinfunction "1_1") (pintype "unspecified"))
      (node (ref "U1") (pin "3") (pinfunction "IN1N_3") (pintype "unspecified"))
    )
    (net (code "31") (name "Net-(U1-IN1P)") (class "Default")
      (node (ref "C3") (pin "2") (pinfunction "2_2") (pintype "unspecified"))
      (node (ref "R1") (pin "2") (pinfunction "2_2") (pintype "unspecified"))
      (node (ref "R2") (pin "2") (pinfunction "2_2") (pintype "unspecified"))
      (node (ref "U1") (pin "4") (pinfunction "IN1P_4") (pintype "unspecified"))
    )
    (net (code "32") (name "Net-(U1-PGA1N)") (class "Default")
      (node (ref "C1") (pin "1") (pinfunction "1_1") (pintype "unspecified"))
      (node (ref "U1") (pin "1") (pinfunction "PGA1N_1") (pintype "unspecified"))
    )
    (net (code "33") (name "Net-(U1-PGA1P)") (class "Default")
      (node (ref "C1") (pin "2") (pinfunction "2_2") (pintype "unspecified"))
      (node (ref "U1") (pin "2") (pinfunction "PGA1P_2") (pintype "unspecified"))
    )
    (net (code "34") (name "Net-(U1-PGA2N)") (class "Default")
      (node (ref "C12") (pin "2") (pinfunction "2_2") (pintype "unspecified"))
      (node (ref "U1") (pin "7") (pinfunction "PGA2N_7") (pintype "unspecified"))
    )
    (net (code "35") (name "Net-(U1-PGA2P)") (class "Default")
      (node (ref "C12") (pin "1") (pinfunction "1_1") (pintype "unspecified"))
      (node (ref "U1") (pin "8") (pinfunction "PGA2P_8") (pintype "unspecified"))
    )
    (net (code "36") (name "Net-(U1-RLDINV)") (class "Default")
      (node (ref "C27") (pin "2") (pinfunction "2_2") (pintype "unspecified"))
      (node (ref "R20") (pin "2") (pinfunction "2_2") (pintype "unspecified"))
      (node (ref "U1") (pin "28") (pinfunction "RLDINV_28") (pintype "unspecified"))
    )
    (net (code "37") (name "Net-(U1-RLDIN{slash}RLDREF)") (class "Default")
      (node (ref "R19") (pin "2") (pinfunction "2_2") (pintype "unspecified"))
      (node (ref "U1") (pin "29") (pinfunction "RLDIN/RLDREF_29") (pintype "unspecified"))
    )
    (net (code "38") (name "Net-(U1-RLDOUT)") (class "Default")
      (node (ref "C27") (pin "1") (pinfunction "1_1") (pintype "unspecified"))
      (node (ref "R19") (pin "1") (pinfunction "1_1") (pintype "unspecified"))
      (node (ref "R20") (pin "1") (pinfunction "1_1") (pintype "unspecified"))
      (node (ref "R21") (pin "2") (pinfunction "2_2") (pintype "unspecified"))
      (node (ref "U1") (pin "30") (pinfunction "RLDOUT_30") (pintype "unspecified"))
    )
    (net (code "39") (name "Net-(U1-VCAP1)") (class "Default")
      (node (ref "C21") (pin "2") (pinfunction "2_2") (pintype "unspecified"))
      (node (ref "U1") (pin "11") (pinfunction "VCAP1_11") (pintype "unspecified"))
    )
    (net (code "40") (name "Net-(U1-VCAP2)") (class "Default")
      (node (ref "C24") (pin "2") (pinfunction "2_2") (pintype "unspecified"))
      (node (ref "U1") (pin "27") (pinfunction "VCAP2_27") (pintype "unspecified"))
    )
    (net (code "41") (name "Net-(U1-VREFP)") (class "Default")
      (node (ref "C19") (pin "2") (pinfunction "2_2") (pintype "unspecified"))
      (node (ref "C20") (pin "2") (pinfunction "2_2") (pintype "unspecified"))
      (node (ref "U1") (pin "9") (pinfunction "VREFP_9") (pintype "unspecified"))
    )
    (net (code "42") (name "Net-(U2-OUT)") (class "Default")
      (node (ref "C13") (pin "2") (pinfunction "2_2") (pintype "unspecified"))
      (node (ref "C16") (pin "2") (pinfunction "2_2") (pintype "unspecified"))
      (node (ref "L3") (pin "1") (pinfunction "1_1") (pintype "unspecified"))
      (node (ref "U2") (pin "5") (pinfunction "OUT_5") (pintype "unspecified"))
    )
    (net (code "43") (name "VCCIN_ADS") (class "Default")
      (node (ref "C14") (pin "2") (pinfunction "2_2") (pintype "unspecified"))
      (node (ref "C15") (pin "2") (pinfunction "2_2") (pintype "unspecified"))
      (node (ref "C28") (pin "2") (pinfunction "2_2") (pintype "input"))
      (node (ref "C29") (pin "2") (pinfunction "2_2") (pintype "input"))
      (node (ref "H7") (pin "2") (pinfunction "2_2") (pintype "input"))
      (node (ref "U2") (pin "1") (pinfunction "IN_1") (pintype "unspecified"))
      (node (ref "U2") (pin "3") (pinfunction "EN_3") (pintype "unspecified"))
      (node (ref "U5") (pin "1") (pinfunction "IN_1") (pintype "unspecified"))
      (node (ref "U5") (pin "3") (pinfunction "EN_3") (pintype "unspecified"))
    )
    (net (code "44") (name "unconnected-(CN2-Pad2)") (class "Default")
      (node (ref "CN2") (pin "2") (pinfunction "2_2") (pintype "input+no_connect"))
    )
    (net (code "45") (name "unconnected-(CN2-Pad5)") (class "Default")
      (node (ref "CN2") (pin "5") (pinfunction "5_5") (pintype "input+no_connect"))
    )
    (net (code "46") (name "unconnected-(CN3-Pad3)") (class "Default")
      (node (ref "CN3") (pin "3") (pinfunction "3_3") (pintype "input+no_connect"))
    )
    (net (code "47") (name "unconnected-(CN3-Pad6)") (class "Default")
      (node (ref "CN3") (pin "6") (pinfunction "6_6") (pintype "input+no_connect"))
    )
    (net (code "48") (name "unconnected-(CN4-Pad3)") (class "Default")
      (node (ref "CN4") (pin "3") (pinfunction "3_3") (pintype "unspecified+no_connect"))
    )
    (net (code "49") (name "unconnected-(CN4-Pad6)") (class "Default")
      (node (ref "CN4") (pin "6") (pinfunction "6_6") (pintype "unspecified+no_connect"))
    )
    (net (code "50") (name "unconnected-(CN4-Pad7)") (class "Default")
      (node (ref "CN4") (pin "7") (pinfunction "7_7") (pintype "unspecified+no_connect"))
    )
    (net (code "51") (name "unconnected-(U2-NR{slash}FB-Pad4)") (class "Default")
      (node (ref "U2") (pin "4") (pinfunction "NR/FB_4") (pintype "unspecified"))
    )
    (net (code "52") (name "unconnected-(U5-N{slash}C-Pad4)") (class "Default")
      (node (ref "U5") (pin "4") (pinfunction "N/C_4") (pintype "unspecified+no_connect"))
    )
  )
)
